# BJTTSFP-4-1_DCBias.net
KiCad netlist of a schematic drawn in Altium Designer
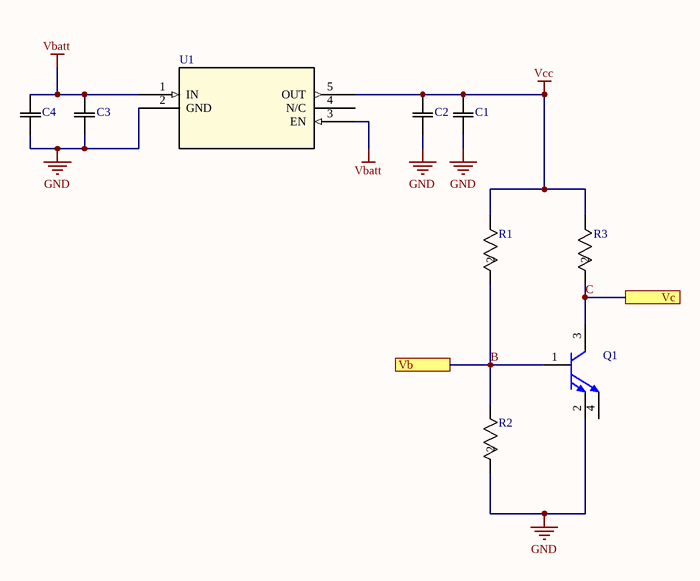
[diagram p0: BJTTSFP-4-1_DCBias.SchDoc]

(export (version "E")
  (design (tool "Eeschema 10.0.6"))
  (components
    (comp (ref "C1")
      (value "~")
      (footprint "YAG_CC0402")
      (description "No Description Available")
      (fields
        (field (name "MANUFACTURER_PART_NUMBER") "CC0402KRX7R9BB103")
        (field (name "COPYRIGHT") "Copyright (C) 2018 Accelerated Designs. All rights reserved")
      )
      (libsource (lib "0402Capacitor_Yageo") (part "CC0402KRX7R9BB10"))
    )
    (comp (ref "C2")
      (value "~")
      (footprint "YAG_CC0402")
      (description "No Description Available")
      (fields
        (field (name "MANUFACTURER_PART_NUMBER") "CC0402KRX7R9BB103")
        (field (name "COPYRIGHT") "Copyright (C) 2018 Accelerated Designs. All rights reserved")
      )
      (libsource (lib "0402Capacitor_Yageo") (part "CC0402KRX7R9BB10"))
    )
    (comp (ref "C3")
      (value "~")
      (footprint "YAG_CC0402")
      (description "No Description Available")
      (fields
        (field (name "MANUFACTURER_PART_NUMBER") "CC0402KRX7R9BB103")
        (field (name "COPYRIGHT") "Copyright (C) 2018 Accelerated Designs. All rights reserved")
      )
      (libsource (lib "0402Capacitor_Yageo") (part "CC0402KRX7R9BB10"))
    )
    (comp (ref "C4")
      (value "~")
      (footprint "YAG_CC0402")
      (description "No Description Available")
      (fields
        (field (name "MANUFACTURER_PART_NUMBER") "CC0402KRX7R9BB103")
        (field (name "COPYRIGHT") "Copyright (C) 2018 Accelerated Designs. All rights reserved")
      )
      (libsource (lib "0402Capacitor_Yageo") (part "CC0402KRX7R9BB10"))
    )
    (comp (ref "Q1")
      (value "~")
      (footprint "INF-TSFP-4-1_V")
      (fields (field (name "MANUFACTURER") "Infineon") (field (name "PARTNUMBER") "BFP720F"))
      (libsource (lib "Infineon_RFBJT_TSFP-4-1") (part "BFP720F"))
    )
    (comp (ref "R1")
      (value "~")
      (footprint "RC0402N")
      (description "No Description Available")
      (fields
        (field (name "MANUFACTURER_PART_NUMBER") "RC0402JR-070RL")
        (field (name "COPYRIGHT") "Copyright (C) 2018 Accelerated Designs. All rights reserved")
      )
      (libsource (lib "Resistor0402Yageo") (part "RC0402JR-070RL"))
    )
    (comp (ref "R2")
      (value "~")
      (footprint "RC0402N")
      (description "No Description Available")
      (fields
        (field (name "MANUFACTURER_PART_NUMBER") "RC0402JR-070RL")
        (field (name "COPYRIGHT") "Copyright (C) 2018 Accelerated Designs. All rights reserved")
      )
      (libsource (lib "Resistor0402Yageo") (part "RC0402JR-070RL"))
    )
    (comp (ref "R3")
      (value "~")
      (footprint "RC0402N")
      (description "No Description Available")
      (fields
        (field (name "MANUFACTURER_PART_NUMBER") "RC0402JR-070RL")
        (field (name "COPYRIGHT") "Copyright (C) 2018 Accelerated Designs. All rights reserved")
      )
      (libsource (lib "Resistor0402Yageo") (part "RC0402JR-070RL"))
    )
    (comp (ref "U1")
      (value "~")
      (footprint "DBV5")
      (description "No Description Available")
      (fields
        (field (name "MANUFACTURER_PART_NUMBER") "LP5907MFX-3.3/NOPB")
        (field (name "COPYRIGHT") "Copyright (C) 2018 Accelerated Designs. All rights reserved")
      )
      (libsource (lib "TI_LDO_3V3_SOT325") (part "LP5907MFX-3.3/NO"))
    )
  )
  (nets
    (net (code "1") (name "/B") (class "Default")
      (node (ref "Q1") (pin "1") (pinfunction "B_1") (pintype "passive"))
      (node (ref "R1") (pin "2") (pinfunction "2_2") (pintype "passive"))
      (node (ref "R2") (pin "1") (pinfunction "1_1") (pintype "passive"))
    )
    (net (code "2") (name "/C") (class "Default")
      (node (ref "Q1") (pin "3") (pinfunction "C_3") (pintype "passive"))
      (node (ref "R3") (pin "2") (pinfunction "2_2") (pintype "passive"))
    )
    (net (code "3") (name "GND") (class "Default")
      (node (ref "C1") (pin "1") (pinfunction "1_1") (pintype "passive"))
      (node (ref "C2") (pin "1") (pinfunction "1_1") (pintype "passive"))
      (node (ref "C3") (pin "1") (pinfunction "1_1") (pintype "passive"))
      (node (ref "C4") (pin "1") (pinfunction "1_1") (pintype "passive"))
      (node (ref "Q1") (pin "2") (pinfunction "E_2") (pintype "passive"))
      (node (ref "R2") (pin "2") (pinfunction "2_2") (pintype "passive"))
      (node (ref "U1") (pin "2") (pinfunction "GND_2") (pintype "power_in"))
    )
    (net (code "4") (name "Vbatt") (class "Default")
      (node (ref "C3") (pin "2") (pinfunction "2_2") (pintype "passive"))
      (node (ref "C4") (pin "2") (pinfunction "2_2") (pintype "passive"))
      (node (ref "U1") (pin "1") (pinfunction "IN_1") (pintype "input"))
      (node (ref "U1") (pin "3") (pinfunction "EN_3") (pintype "input"))
    )
    (net (code "5") (name "Vcc") (class "Default")
      (node (ref "C1") (pin "2") (pinfunction "2_2") (pintype "passive"))
      (node (ref "C2") (pin "2") (pinfunction "2_2") (pintype "passive"))
      (node (ref "R1") (pin "1") (pinfunction "1_1") (pintype "passive"))
      (node (ref "R3") (pin "1") (pinfunction "1_1") (pintype "passive"))
      (node (ref "U1") (pin "5") (pinfunction "OUT_5") (pintype "output"))
    )
    (net (code "6") (name "unconnected-(Q1-E-Pad4)") (class "Default")
      (node (ref "Q1") (pin "4") (pinfunction "E_4") (pintype "passive"))
    )
    (net (code "7") (name "unconnected-(U1-N{slash}C-Pad4)") (class "Default")
      (node (ref "U1") (pin "4") (pinfunction "N/C_4") (pintype "passive"))
    )
  )
)
